# USB-HUB-V2_0.net
KiCad netlist of a schematic drawn in EasyEDA Pro
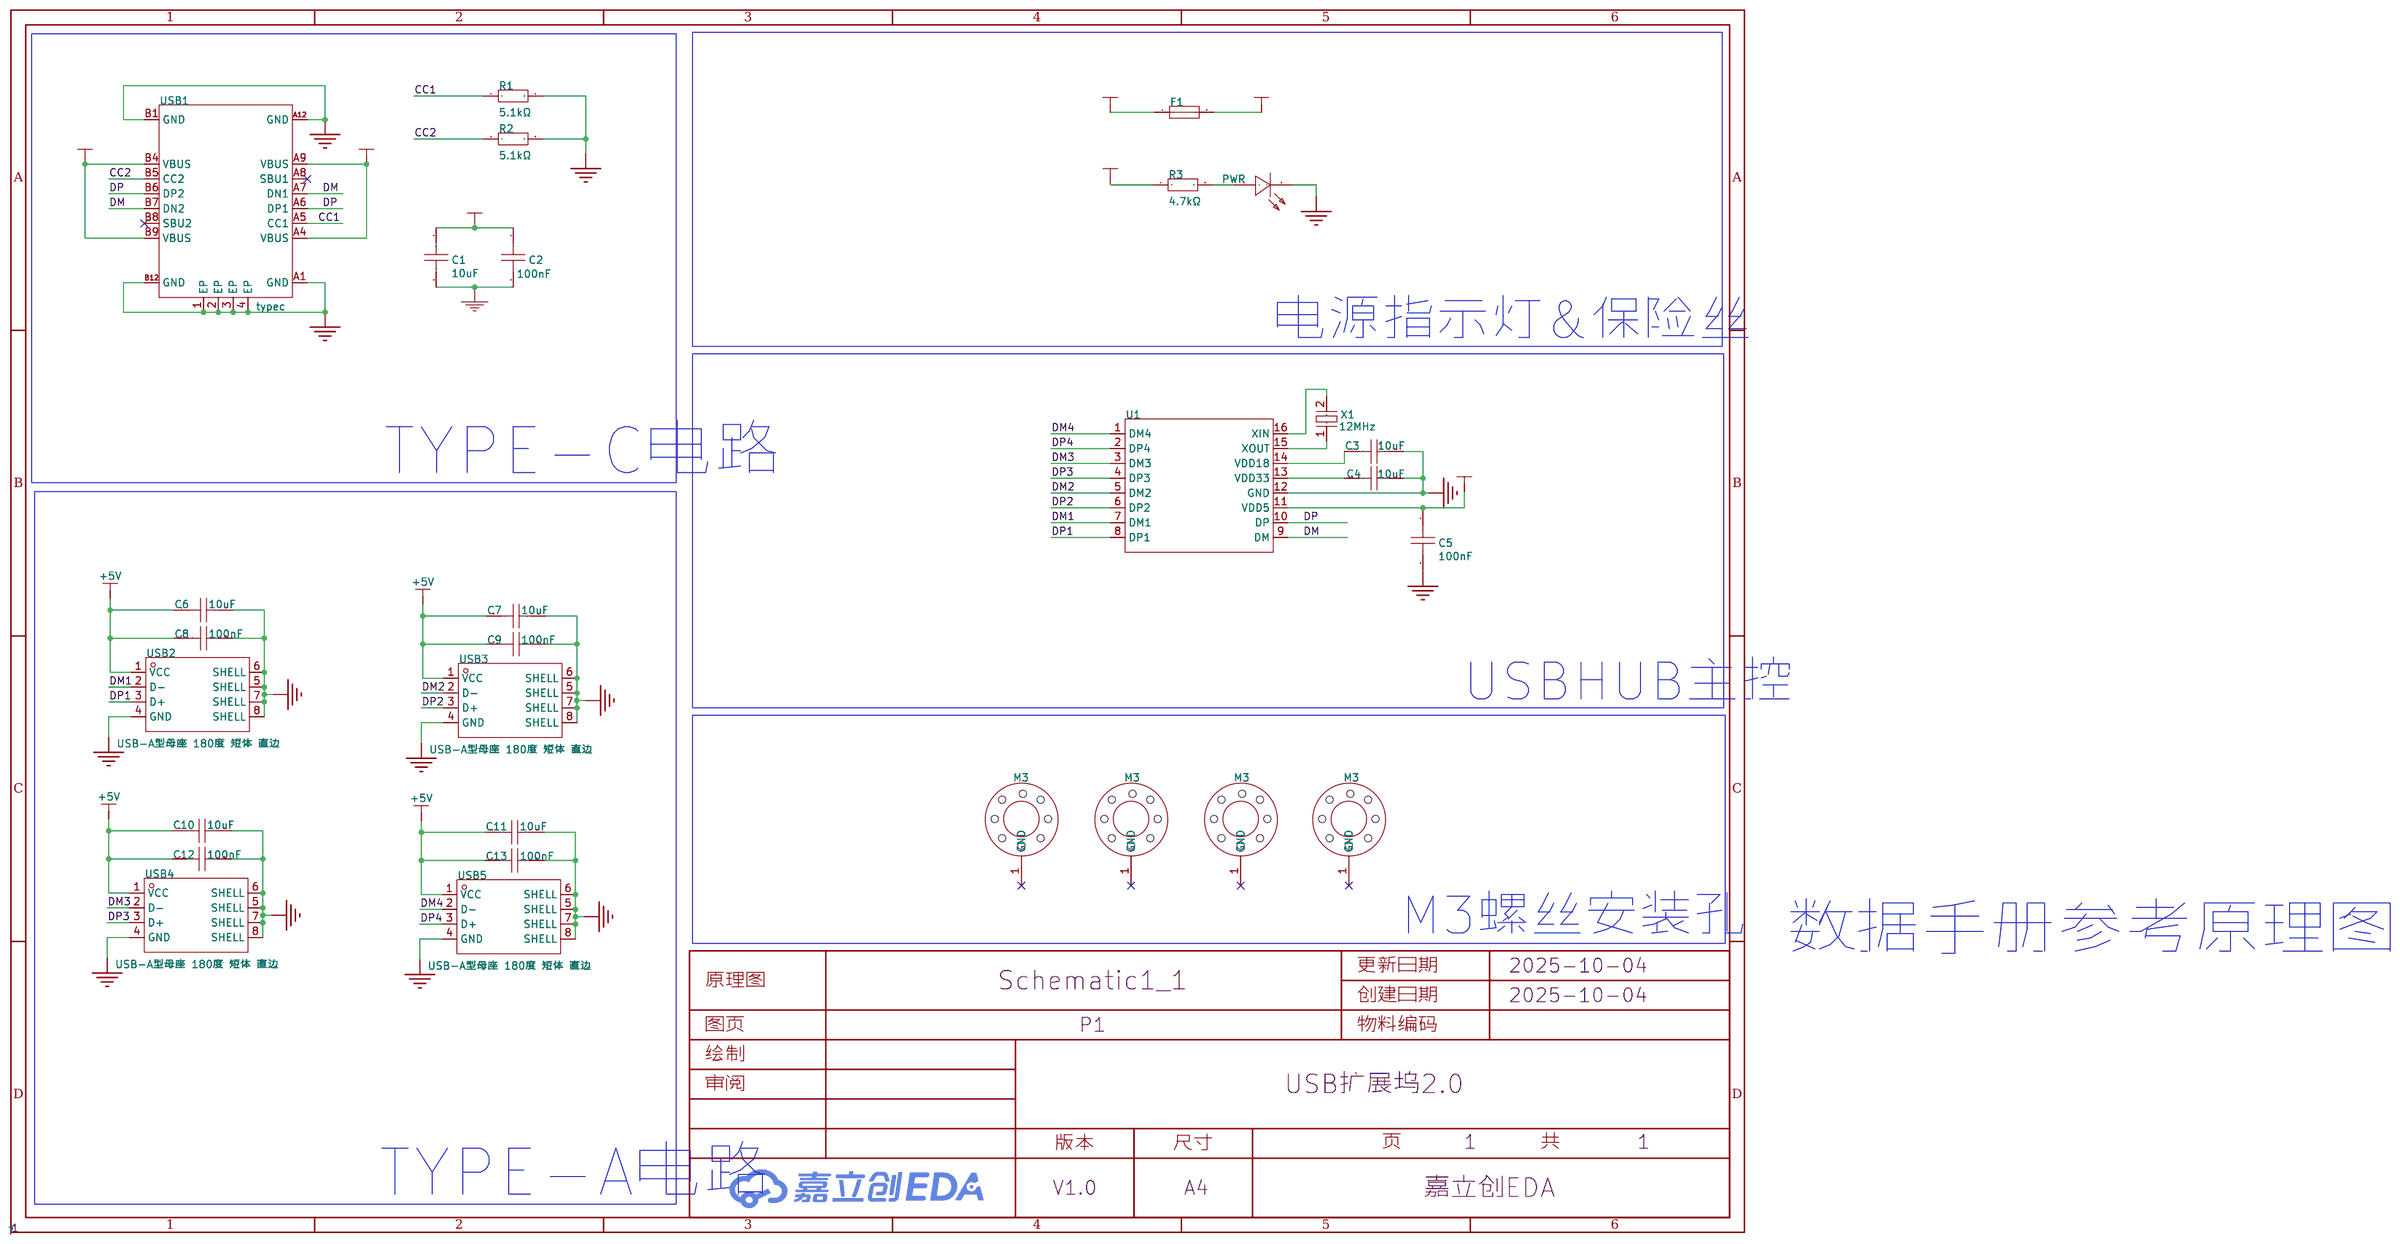
[diagram p0: schematic sheet]

(export (version "E")
  (design (tool "Eeschema 10.0.6"))
  (components
    (comp (ref "C1")
      (value "10uF")
      (fields (field (name "Manufacturer") "SAMSUNG(三星)"))
      (libsource (lib "easyedapro") (part "10uF"))
    )
    (comp (ref "C2")
      (value "100nF")
      (fields (field (name "Manufacturer") "FH(风华)"))
      (libsource (lib "easyedapro") (part "0.1uF"))
    )
    (comp (ref "C3")
      (value "10uF")
      (footprint "easyedapro:C0805")
      (description "容值:10uF;精度:±10%;额定电压:50V;温度系数:X5R;")
      (fields
        (field (name "Manufacturer Part") "CL21A106KBYQNNE")
        (field (name "Manufacturer") "SAMSUNG(三星)")
      )
      (libsource (lib "easyedapro") (part "CL21A106KBYQNNE"))
    )
    (comp (ref "C4")
      (value "10uF")
      (footprint "easyedapro:C0805")
      (description "容值:10uF;精度:±10%;额定电压:50V;温度系数:X5R;")
      (fields
        (field (name "Manufacturer Part") "CL21A106KBYQNNE")
        (field (name "Manufacturer") "SAMSUNG(三星)")
      )
      (libsource (lib "easyedapro") (part "CL21A106KBYQNNE"))
    )
    (comp (ref "C5")
      (value "100nF")
      (fields (field (name "Manufacturer") "FH(风华)"))
      (libsource (lib "easyedapro") (part "0.1uF"))
    )
    (comp (ref "C6")
      (value "10uF")
      (fields (field (name "Manufacturer") "SAMSUNG(三星)"))
      (libsource (lib "easyedapro") (part "10uF"))
    )
    (comp (ref "C7")
      (value "10uF")
      (fields (field (name "Manufacturer") "SAMSUNG(三星)"))
      (libsource (lib "easyedapro") (part "10uF"))
    )
    (comp (ref "C8")
      (value "100nF")
      (fields (field (name "Manufacturer") "FH(风华)"))
      (libsource (lib "easyedapro") (part "0.1uF"))
    )
    (comp (ref "C9")
      (value "100nF")
      (fields (field (name "Manufacturer") "FH(风华)"))
      (libsource (lib "easyedapro") (part "0.1uF"))
    )
    (comp (ref "C10")
      (value "10uF")
      (fields (field (name "Manufacturer") "SAMSUNG(三星)"))
      (libsource (lib "easyedapro") (part "10uF"))
    )
    (comp (ref "C11")
      (value "10uF")
      (fields (field (name "Manufacturer") "SAMSUNG(三星)"))
      (libsource (lib "easyedapro") (part "10uF"))
    )
    (comp (ref "C12")
      (value "100nF")
      (fields (field (name "Manufacturer") "FH(风华)"))
      (libsource (lib "easyedapro") (part "0.1uF"))
    )
    (comp (ref "C13")
      (value "100nF")
      (fields (field (name "Manufacturer") "FH(风华)"))
      (libsource (lib "easyedapro") (part "0.1uF"))
    )
    (comp (ref "F1")
      (value "BSMD1206-150-12V")
      (footprint "easyedapro:F1206")
      (description "耐压(Vmax):12V;最大电流(Imax):40A;保持电流(Ihold):1.5A;跳闸电流(Itrip):3A;")
      (fields (field (name "Manufacturer") "BHFUSE(佰宏)"))
      (libsource (lib "easyedapro") (part "BSMD1206-150-12V"))
    )
    (comp (ref "hole1")
      (value "M3")
      (footprint "easyedapro:m3梅花孔")
      (description "梅花螺丝孔")
      (libsource (lib "easyedapro") (part "m3_梅花螺丝孔"))
    )
    (comp (ref "hole2")
      (value "M3")
      (footprint "easyedapro:m3梅花孔")
      (description "梅花螺丝孔")
      (libsource (lib "easyedapro") (part "m3_梅花螺丝孔"))
    )
    (comp (ref "hole3")
      (value "M3")
      (footprint "easyedapro:m3梅花孔")
      (description "梅花螺丝孔")
      (libsource (lib "easyedapro") (part "m3_梅花螺丝孔"))
    )
    (comp (ref "hole4")
      (value "M3")
      (footprint "easyedapro:m3梅花孔")
      (description "梅花螺丝孔")
      (libsource (lib "easyedapro") (part "m3_梅花螺丝孔"))
    )
    (comp (ref "PWR")
      (value "NCD0805R1")
      (footprint "easyedapro:LED0805-R-RD")
      (fields (field (name "Manufacturer") "国星光电"))
      (libsource (lib "easyedapro") (part "FC-2012HRK-620D"))
    )
    (comp (ref "R1")
      (value "5.1kΩ")
      (footprint "easyedapro:R0805")
      (description "电阻类型:厚膜电阻;阻值:5.1kΩ;精度:±1%;功率:125mW;工作电压:150V;温度系数:±100ppm/°C;")
      (fields
        (field (name "Manufacturer Part") "0805W8F5101T5E")
        (field (name "Manufacturer") "UNI-ROYAL(厚声)")
      )
      (libsource (lib "easyedapro") (part "0805W8F5101T5E"))
    )
    (comp (ref "R2")
      (value "5.1kΩ")
      (footprint "easyedapro:R0805")
      (description "电阻类型:厚膜电阻;阻值:5.1kΩ;精度:±1%;功率:125mW;工作电压:150V;温度系数:±100ppm/°C;")
      (fields
        (field (name "Manufacturer Part") "0805W8F5101T5E")
        (field (name "Manufacturer") "UNI-ROYAL(厚声)")
      )
      (libsource (lib "easyedapro") (part "0805W8F5101T5E"))
    )
    (comp (ref "R3")
      (value "4.7kΩ")
      (footprint "easyedapro:R0805")
      (description "电阻类型:厚膜电阻;阻值:4.7kΩ;精度:±1%;功率:125mW;最大工作电压:150V;温度系数:±100ppm/°C;")
      (fields
        (field (name "Manufacturer Part") "0805W8F4701T5E")
        (field (name "Manufacturer") "UNI-ROYAL(厚声)")
      )
      (libsource (lib "easyedapro") (part "0805W8F4701T5E"))
    )
    (comp (ref "U1") (value "SL2.1A") (libsource (lib "easyedapro") (part "SL2.1A")))
    (comp (ref "USB1")
      (value "typec")
      (footprint "easyedapro:USB-C-SMD_KH-TYPE-C-16P")
      (libsource (lib "easyedapro") (part "TYPEC_C9900016956"))
    )
    (comp (ref "USB2")
      (value "USB-A型母座 180度 短体 直边")
      (footprint "easyedapro:USB-A-SMD_WT_C9900004571")
      (libsource (lib "easyedapro") (part "USB-A型母座 180度 短体 直边"))
    )
    (comp (ref "USB3")
      (value "USB-A型母座 180度 短体 直边")
      (footprint "easyedapro:USB-A-SMD_WT_C9900004571")
      (libsource (lib "easyedapro") (part "USB-A型母座 180度 短体 直边"))
    )
    (comp (ref "USB4")
      (value "USB-A型母座 180度 短体 直边")
      (footprint "easyedapro:USB-A-SMD_WT_C9900004571")
      (libsource (lib "easyedapro") (part "USB-A型母座 180度 短体 直边"))
    )
    (comp (ref "USB5")
      (value "USB-A型母座 180度 短体 直边")
      (footprint "easyedapro:USB-A-SMD_WT_C9900004571")
      (libsource (lib "easyedapro") (part "USB-A型母座 180度 短体 直边"))
    )
    (comp (ref "X1")
      (value "12MHz")
      (footprint "easyedapro:CRYSTAL-SMD_L5.0-W3.2-1")
      (description "频率:12MHz;负载电容:20pF;频率稳定度:±10ppm;")
      (fields
        (field (name "Manufacturer Part") "HY12MSMD5032TCOB1R10")
        (field (name "Manufacturer") "Huiyuan crystal(惠源晶工)")
      )
      (libsource (lib "easyedapro") (part "HY12MSMD5032TCOB1R10"))
    )
  )
  (nets
    (net (code "1") (name "+5V") (class "Default")
      (node (ref "C10") (pin "1") (pinfunction "1_1") (pintype "unspecified"))
      (node (ref "C11") (pin "1") (pinfunction "1_1") (pintype "unspecified"))
      (node (ref "C12") (pin "1") (pinfunction "1_1") (pintype "unspecified"))
      (node (ref "C13") (pin "1") (pinfunction "1_1") (pintype "unspecified"))
      (node (ref "C5") (pin "1") (pinfunction "1_1") (pintype "unspecified"))
      (node (ref "C6") (pin "1") (pinfunction "1_1") (pintype "unspecified"))
      (node (ref "C7") (pin "1") (pinfunction "1_1") (pintype "unspecified"))
      (node (ref "C8") (pin "1") (pinfunction "1_1") (pintype "unspecified"))
      (node (ref "C9") (pin "1") (pinfunction "1_1") (pintype "unspecified"))
      (node (ref "F1") (pin "2") (pinfunction "2_2") (pintype "unspecified"))
      (node (ref "R3") (pin "1") (pinfunction "1_1") (pintype "input"))
      (node (ref "U1") (pin "11") (pinfunction "VDD5_11") (pintype "unspecified"))
      (node (ref "USB2") (pin "1") (pinfunction "VCC_1") (pintype "unspecified"))
      (node (ref "USB3") (pin "1") (pinfunction "VCC_1") (pintype "unspecified"))
      (node (ref "USB4") (pin "1") (pinfunction "VCC_1") (pintype "unspecified"))
      (node (ref "USB5") (pin "1") (pinfunction "VCC_1") (pintype "unspecified"))
    )
    (net (code "2") (name "/CC1") (class "Default")
      (node (ref "R1") (pin "1") (pinfunction "1_1") (pintype "input"))
      (node (ref "USB1") (pin "A5") (pinfunction "CC1_A5") (pintype "unspecified"))
    )
    (net (code "3") (name "/CC2") (class "Default")
      (node (ref "R2") (pin "1") (pinfunction "1_1") (pintype "input"))
      (node (ref "USB1") (pin "B5") (pinfunction "CC2_B5") (pintype "unspecified"))
    )
    (net (code "4") (name "/DM") (class "Default")
      (node (ref "U1") (pin "9") (pinfunction "DM_9") (pintype "unspecified"))
      (node (ref "USB1") (pin "A7") (pinfunction "DN1_A7") (pintype "unspecified"))
      (node (ref "USB1") (pin "B7") (pinfunction "DN2_B7") (pintype "unspecified"))
    )
    (net (code "5") (name "/DM1") (class "Default")
      (node (ref "U1") (pin "7") (pinfunction "DM1_7") (pintype "unspecified"))
      (node (ref "USB2") (pin "2") (pinfunction "D-_2") (pintype "unspecified"))
    )
    (net (code "6") (name "/DM2") (class "Default")
      (node (ref "U1") (pin "5") (pinfunction "DM2_5") (pintype "unspecified"))
      (node (ref "USB3") (pin "2") (pinfunction "D-_2") (pintype "unspecified"))
    )
    (net (code "7") (name "/DM3") (class "Default")
      (node (ref "U1") (pin "3") (pinfunction "DM3_3") (pintype "unspecified"))
      (node (ref "USB4") (pin "2") (pinfunction "D-_2") (pintype "unspecified"))
    )
    (net (code "8") (name "/DM4") (class "Default")
      (node (ref "U1") (pin "1") (pinfunction "DM4_1") (pintype "unspecified"))
      (node (ref "USB5") (pin "2") (pinfunction "D-_2") (pintype "unspecified"))
    )
    (net (code "9") (name "/DP") (class "Default")
      (node (ref "U1") (pin "10") (pinfunction "DP_10") (pintype "unspecified"))
      (node (ref "USB1") (pin "A6") (pinfunction "DP1_A6") (pintype "unspecified"))
      (node (ref "USB1") (pin "B6") (pinfunction "DP2_B6") (pintype "unspecified"))
    )
    (net (code "10") (name "/DP1") (class "Default")
      (node (ref "U1") (pin "8") (pinfunction "DP1_8") (pintype "unspecified"))
      (node (ref "USB2") (pin "3") (pinfunction "D+_3") (pintype "unspecified"))
    )
    (net (code "11") (name "/DP2") (class "Default")
      (node (ref "U1") (pin "6") (pinfunction "DP2_6") (pintype "unspecified"))
      (node (ref "USB3") (pin "3") (pinfunction "D+_3") (pintype "unspecified"))
    )
    (net (code "12") (name "/DP3") (class "Default")
      (node (ref "U1") (pin "4") (pinfunction "DP3_4") (pintype "unspecified"))
      (node (ref "USB4") (pin "3") (pinfunction "D+_3") (pintype "unspecified"))
    )
    (net (code "13") (name "/DP4") (class "Default")
      (node (ref "U1") (pin "2") (pinfunction "DP4_2") (pintype "unspecified"))
      (node (ref "USB5") (pin "3") (pinfunction "D+_3") (pintype "unspecified"))
    )
    (net (code "14") (name "GND") (class "Default")
      (node (ref "C1") (pin "2") (pinfunction "2_2") (pintype "unspecified"))
      (node (ref "C10") (pin "2") (pinfunction "2_2") (pintype "unspecified"))
      (node (ref "C11") (pin "2") (pinfunction "2_2") (pintype "unspecified"))
      (node (ref "C12") (pin "2") (pinfunction "2_2") (pintype "unspecified"))
      (node (ref "C13") (pin "2") (pinfunction "2_2") (pintype "unspecified"))
      (node (ref "C2") (pin "2") (pinfunction "2_2") (pintype "unspecified"))
      (node (ref "C3") (pin "2") (pinfunction "2_2") (pintype "unspecified"))
      (node (ref "C4") (pin "2") (pinfunction "2_2") (pintype "unspecified"))
      (node (ref "C5") (pin "2") (pinfunction "2_2") (pintype "unspecified"))
      (node (ref "C6") (pin "2") (pinfunction "2_2") (pintype "unspecified"))
      (node (ref "C7") (pin "2") (pinfunction "2_2") (pintype "unspecified"))
      (node (ref "C8") (pin "2") (pinfunction "2_2") (pintype "unspecified"))
      (node (ref "C9") (pin "2") (pinfunction "2_2") (pintype "unspecified"))
      (node (ref "PWR") (pin "2") (pinfunction "-_2") (pintype "unspecified"))
      (node (ref "R1") (pin "2") (pinfunction "2_2") (pintype "input"))
      (node (ref "R2") (pin "2") (pinfunction "2_2") (pintype "input"))
      (node (ref "U1") (pin "12") (pinfunction "GND_12") (pintype "unspecified"))
      (node (ref "USB1") (pin "1") (pinfunction "EP_1") (pintype "unspecified"))
      (node (ref "USB1") (pin "2") (pinfunction "EP_2") (pintype "unspecified"))
      (node (ref "USB1") (pin "3") (pinfunction "EP_3") (pintype "unspecified"))
      (node (ref "USB1") (pin "4") (pinfunction "EP_4") (pintype "unspecified"))
      (node (ref "USB1") (pin "A1") (pinfunction "GND_A1") (pintype "unspecified"))
      (node (ref "USB1") (pin "A12") (pinfunction "GND_A12") (pintype "unspecified"))
      (node (ref "USB1") (pin "B1") (pinfunction "GND_B1") (pintype "unspecified"))
      (node (ref "USB1") (pin "B12") (pinfunction "GND_B12") (pintype "unspecified"))
      (node (ref "USB2") (pin "4") (pinfunction "GND_4") (pintype "unspecified"))
      (node (ref "USB2") (pin "5") (pinfunction "SHELL_5") (pintype "unspecified"))
      (node (ref "USB2") (pin "6") (pinfunction "SHELL_6") (pintype "unspecified"))
      (node (ref "USB2") (pin "7") (pinfunction "SHELL_7") (pintype "unspecified"))
      (node (ref "USB2") (pin "8") (pinfunction "SHELL_8") (pintype "unspecified"))
      (node (ref "USB3") (pin "4") (pinfunction "GND_4") (pintype "unspecified"))
      (node (ref "USB3") (pin "5") (pinfunction "SHELL_5") (pintype "unspecified"))
      (node (ref "USB3") (pin "6") (pinfunction "SHELL_6") (pintype "unspecified"))
      (node (ref "USB3") (pin "7") (pinfunction "SHELL_7") (pintype "unspecified"))
      (node (ref "USB3") (pin "8") (pinfunction "SHELL_8") (pintype "unspecified"))
      (node (ref "USB4") (pin "4") (pinfunction "GND_4") (pintype "unspecified"))
      (node (ref "USB4") (pin "5") (pinfunction "SHELL_5") (pintype "unspecified"))
      (node (ref "USB4") (pin "6") (pinfunction "SHELL_6") (pintype "unspecified"))
      (node (ref "USB4") (pin "7") (pinfunction "SHELL_7") (pintype "unspecified"))
      (node (ref "USB4") (pin "8") (pinfunction "SHELL_8") (pintype "unspecified"))
      (node (ref "USB5") (pin "4") (pinfunction "GND_4") (pintype "unspecified"))
      (node (ref "USB5") (pin "5") (pinfunction "SHELL_5") (pintype "unspecified"))
      (node (ref "USB5") (pin "6") (pinfunction "SHELL_6") (pintype "unspecified"))
      (node (ref "USB5") (pin "7") (pinfunction "SHELL_7") (pintype "unspecified"))
      (node (ref "USB5") (pin "8") (pinfunction "SHELL_8") (pintype "unspecified"))
    )
    (net (code "15") (name "Net-(PWR-+)") (class "Default")
      (node (ref "PWR") (pin "1") (pinfunction "+_1") (pintype "unspecified"))
      (node (ref "R3") (pin "2") (pinfunction "2_2") (pintype "input"))
    )
    (net (code "16") (name "Net-(U1-VDD18)") (class "Default")
      (node (ref "C3") (pin "1") (pinfunction "1_1") (pintype "unspecified"))
      (node (ref "U1") (pin "14") (pinfunction "VDD18_14") (pintype "unspecified"))
    )
    (net (code "17") (name "Net-(U1-VDD33)") (class "Default")
      (node (ref "C4") (pin "1") (pinfunction "1_1") (pintype "unspecified"))
      (node (ref "U1") (pin "13") (pinfunction "VDD33_13") (pintype "unspecified"))
    )
    (net (code "18") (name "Net-(U1-XIN)") (class "Default")
      (node (ref "U1") (pin "16") (pinfunction "XIN_16") (pintype "unspecified"))
      (node (ref "X1") (pin "2") (pinfunction "GND_2") (pintype "input"))
    )
    (net (code "19") (name "Net-(U1-XOUT)") (class "Default")
      (node (ref "U1") (pin "15") (pinfunction "XOUT_15") (pintype "unspecified"))
      (node (ref "X1") (pin "1") (pinfunction "1_1") (pintype "input"))
    )
    (net (code "20") (name "VBUS") (class "Default")
      (node (ref "C1") (pin "1") (pinfunction "1_1") (pintype "unspecified"))
      (node (ref "C2") (pin "1") (pinfunction "1_1") (pintype "unspecified"))
      (node (ref "F1") (pin "1") (pinfunction "1_1") (pintype "unspecified"))
      (node (ref "USB1") (pin "A4") (pinfunction "VBUS_A4") (pintype "unspecified"))
      (node (ref "USB1") (pin "A9") (pinfunction "VBUS_A9") (pintype "unspecified"))
      (node (ref "USB1") (pin "B4") (pinfunction "VBUS_B4") (pintype "unspecified"))
      (node (ref "USB1") (pin "B9") (pinfunction "VBUS_B9") (pintype "unspecified"))
    )
    (net (code "21") (name "unconnected-(USB1-SBU1-PadA8)") (class "Default")
      (node (ref "USB1") (pin "A8") (pinfunction "SBU1_A8") (pintype "unspecified+no_connect"))
    )
    (net (code "22") (name "unconnected-(USB1-SBU2-PadB8)") (class "Default")
      (node (ref "USB1") (pin "B8") (pinfunction "SBU2_B8") (pintype "unspecified+no_connect"))
    )
    (net (code "23") (name "unconnected-(hole1-GND-Pad1)") (class "Default")
      (node (ref "hole1") (pin "1") (pinfunction "GND_1") (pintype "input+no_connect"))
    )
    (net (code "24") (name "unconnected-(hole2-GND-Pad1)") (class "Default")
      (node (ref "hole2") (pin "1") (pinfunction "GND_1") (pintype "input+no_connect"))
    )
    (net (code "25") (name "unconnected-(hole3-GND-Pad1)") (class "Default")
      (node (ref "hole3") (pin "1") (pinfunction "GND_1") (pintype "input+no_connect"))
    )
    (net (code "26") (name "unconnected-(hole4-GND-Pad1)") (class "Default")
      (node (ref "hole4") (pin "1") (pinfunction "GND_1") (pintype "input+no_connect"))
    )
  )
)
